# InterfacesB_CONNECTORS.net
KiCad netlist of a schematic drawn in Altium Designer
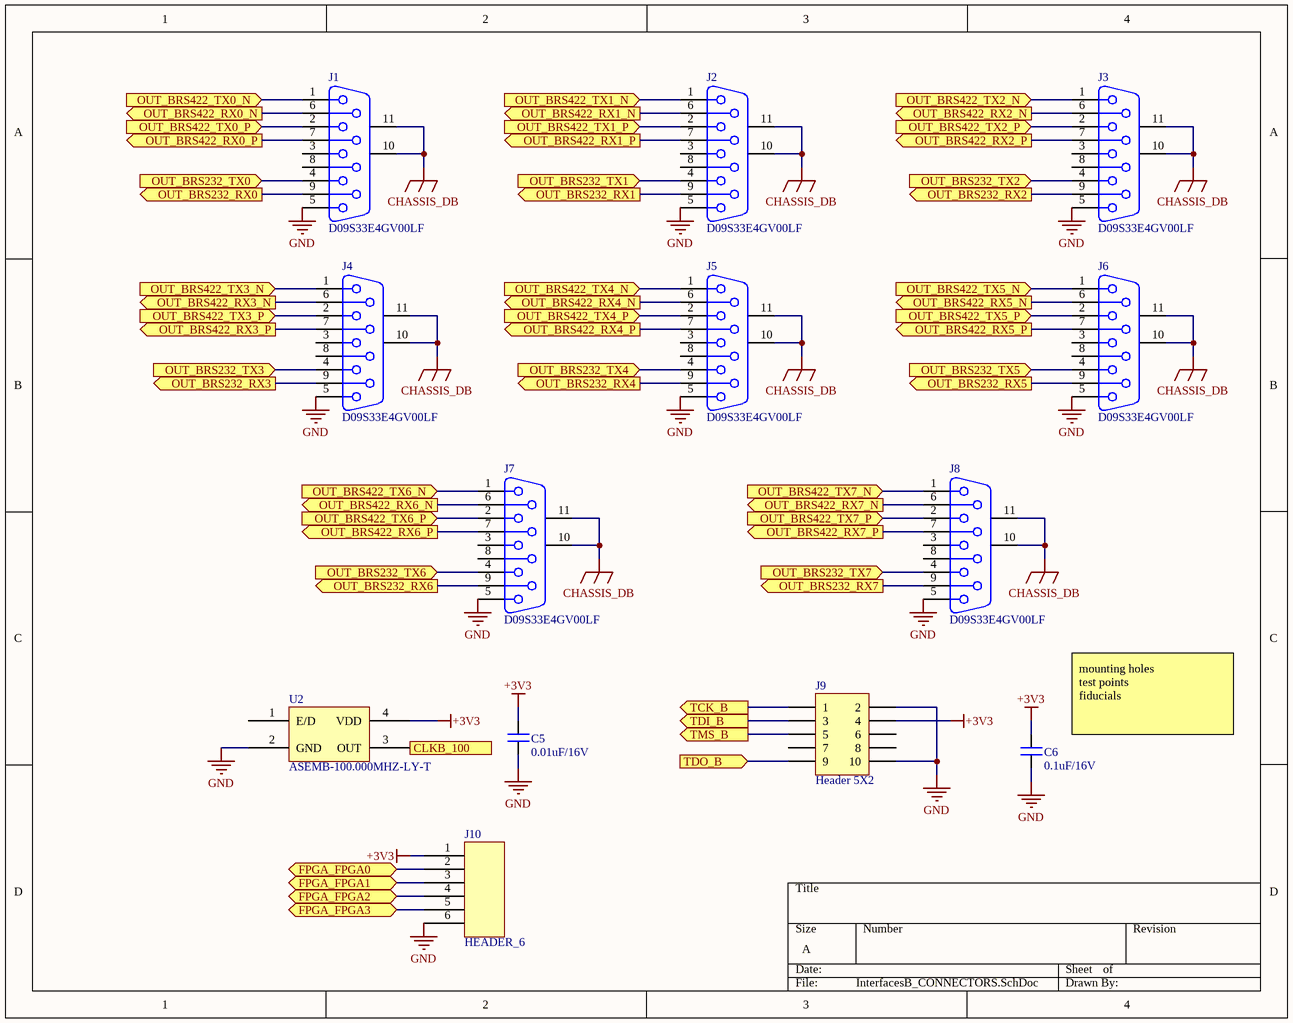
[diagram p0: InterfacesB_CONNECTORS.SchDoc]

(export (version "E")
  (design (tool "Eeschema 10.0.6"))
  (components
    (comp (ref "C5")
      (value "0.01uF/16V")
      (footprint "CAP_0805")
      (fields (field (name "Comment") "CAP_0805"))
      (libsource (lib "AdapterLib") (part "CAP_0805"))
    )
    (comp (ref "C6")
      (value "0.1uF/16V")
      (footprint "CAP_0805")
      (fields (field (name "Comment") "CAP_0805"))
      (libsource (lib "AdapterLib") (part "CAP_0805"))
    )
    (comp (ref "J1")
      (value "D09S33E4GV00LF")
      (footprint "D09S33E4GV00LF")
      (libsource (lib "AdapterLib") (part "D09S33E4GV00LF"))
    )
    (comp (ref "J2")
      (value "D09S33E4GV00LF")
      (footprint "D09S33E4GV00LF")
      (libsource (lib "AdapterLib") (part "D09S33E4GV00LF"))
    )
    (comp (ref "J3")
      (value "D09S33E4GV00LF")
      (footprint "D09S33E4GV00LF")
      (libsource (lib "AdapterLib") (part "D09S33E4GV00LF"))
    )
    (comp (ref "J4")
      (value "D09S33E4GV00LF")
      (footprint "D09S33E4GV00LF")
      (libsource (lib "AdapterLib") (part "D09S33E4GV00LF"))
    )
    (comp (ref "J5")
      (value "D09S33E4GV00LF")
      (footprint "D09S33E4GV00LF")
      (libsource (lib "AdapterLib") (part "D09S33E4GV00LF"))
    )
    (comp (ref "J6")
      (value "D09S33E4GV00LF")
      (footprint "D09S33E4GV00LF")
      (libsource (lib "AdapterLib") (part "D09S33E4GV00LF"))
    )
    (comp (ref "J7")
      (value "D09S33E4GV00LF")
      (footprint "D09S33E4GV00LF")
      (libsource (lib "AdapterLib") (part "D09S33E4GV00LF"))
    )
    (comp (ref "J8")
      (value "D09S33E4GV00LF")
      (footprint "D09S33E4GV00LF")
      (libsource (lib "AdapterLib") (part "D09S33E4GV00LF"))
    )
    (comp (ref "J9")
      (value "Header 5X2")
      (footprint "HEADER 5x2")
      (description "Header, 5-Pin, Dual row")
      (fields (field (name "PUBLISHER") "Altium Limited"))
      (libsource (lib "AdapterLib") (part "Header 5X2"))
    )
    (comp (ref "J10")
      (value "HEADER_6")
      (footprint "HEADER_6")
      (libsource (lib "AdapterLib") (part "HEADER_6"))
    )
    (comp (ref "U2")
      (value "ASEMB-100.000MHZ-LY-T")
      (footprint "ASEMB-100.000MHZ-LY-T")
      (libsource (lib "AdapterLib") (part "ASEMB-100.000MHZ-LY-T"))
    )
  )
  (nets
    (net (code "1") (name "+3V3") (class "Default")
      (node (ref "C5") (pin "2") (pinfunction "2_2") (pintype "passive"))
      (node (ref "C6") (pin "2") (pinfunction "2_2") (pintype "passive"))
      (node (ref "J10") (pin "1") (pintype "passive"))
      (node (ref "J9") (pin "4") (pinfunction "4_4") (pintype "passive"))
      (node (ref "U2") (pin "4") (pinfunction "VDD_4") (pintype "passive"))
    )
    (net (code "2") (name "/CLKB_100") (class "Default")
      (node (ref "U2") (pin "3") (pinfunction "OUT_3") (pintype "passive"))
    )
    (net (code "3") (name "/FPGA_FPGA0") (class "Default") (node (ref "J10") (pin "2") (pintype "passive")))
    (net (code "4") (name "/FPGA_FPGA1") (class "Default") (node (ref "J10") (pin "3") (pintype "passive")))
    (net (code "5") (name "/FPGA_FPGA2") (class "Default") (node (ref "J10") (pin "4") (pintype "passive")))
    (net (code "6") (name "/FPGA_FPGA3") (class "Default") (node (ref "J10") (pin "5") (pintype "passive")))
    (net (code "7") (name "/OUT_BRS232_RX0") (class "Default")
      (node (ref "J1") (pin "9") (pinfunction "9_9") (pintype "passive"))
    )
    (net (code "8") (name "/OUT_BRS232_RX1") (class "Default")
      (node (ref "J2") (pin "9") (pinfunction "9_9") (pintype "passive"))
    )
    (net (code "9") (name "/OUT_BRS232_RX2") (class "Default")
      (node (ref "J3") (pin "9") (pinfunction "9_9") (pintype "passive"))
    )
    (net (code "10") (name "/OUT_BRS232_RX3") (class "Default")
      (node (ref "J4") (pin "9") (pinfunction "9_9") (pintype "passive"))
    )
    (net (code "11") (name "/OUT_BRS232_RX4") (class "Default")
      (node (ref "J5") (pin "9") (pinfunction "9_9") (pintype "passive"))
    )
    (net (code "12") (name "/OUT_BRS232_RX5") (class "Default")
      (node (ref "J6") (pin "9") (pinfunction "9_9") (pintype "passive"))
    )
    (net (code "13") (name "/OUT_BRS232_RX6") (class "Default")
      (node (ref "J7") (pin "9") (pinfunction "9_9") (pintype "passive"))
    )
    (net (code "14") (name "/OUT_BRS232_RX7") (class "Default")
      (node (ref "J8") (pin "9") (pinfunction "9_9") (pintype "passive"))
    )
    (net (code "15") (name "/OUT_BRS232_TX0") (class "Default")
      (node (ref "J1") (pin "4") (pinfunction "4_4") (pintype "passive"))
    )
    (net (code "16") (name "/OUT_BRS232_TX1") (class "Default")
      (node (ref "J2") (pin "4") (pinfunction "4_4") (pintype "passive"))
    )
    (net (code "17") (name "/OUT_BRS232_TX2") (class "Default")
      (node (ref "J3") (pin "4") (pinfunction "4_4") (pintype "passive"))
    )
    (net (code "18") (name "/OUT_BRS232_TX3") (class "Default")
      (node (ref "J4") (pin "4") (pinfunction "4_4") (pintype "passive"))
    )
    (net (code "19") (name "/OUT_BRS232_TX4") (class "Default")
      (node (ref "J5") (pin "4") (pinfunction "4_4") (pintype "passive"))
    )
    (net (code "20") (name "/OUT_BRS232_TX5") (class "Default")
      (node (ref "J6") (pin "4") (pinfunction "4_4") (pintype "passive"))
    )
    (net (code "21") (name "/OUT_BRS232_TX6") (class "Default")
      (node (ref "J7") (pin "4") (pinfunction "4_4") (pintype "passive"))
    )
    (net (code "22") (name "/OUT_BRS232_TX7") (class "Default")
      (node (ref "J8") (pin "4") (pinfunction "4_4") (pintype "passive"))
    )
    (net (code "23") (name "/OUT_BRS422_RX0_N") (class "Default")
      (node (ref "J1") (pin "6") (pinfunction "6_6") (pintype "passive"))
    )
    (net (code "24") (name "/OUT_BRS422_RX0_P") (class "Default")
      (node (ref "J1") (pin "7") (pinfunction "7_7") (pintype "passive"))
    )
    (net (code "25") (name "/OUT_BRS422_RX1_N") (class "Default")
      (node (ref "J2") (pin "6") (pinfunction "6_6") (pintype "passive"))
    )
    (net (code "26") (name "/OUT_BRS422_RX1_P") (class "Default")
      (node (ref "J2") (pin "7") (pinfunction "7_7") (pintype "passive"))
    )
    (net (code "27") (name "/OUT_BRS422_RX2_N") (class "Default")
      (node (ref "J3") (pin "6") (pinfunction "6_6") (pintype "passive"))
    )
    (net (code "28") (name "/OUT_BRS422_RX2_P") (class "Default")
      (node (ref "J3") (pin "7") (pinfunction "7_7") (pintype "passive"))
    )
    (net (code "29") (name "/OUT_BRS422_RX3_N") (class "Default")
      (node (ref "J4") (pin "6") (pinfunction "6_6") (pintype "passive"))
    )
    (net (code "30") (name "/OUT_BRS422_RX3_P") (class "Default")
      (node (ref "J4") (pin "7") (pinfunction "7_7") (pintype "passive"))
    )
    (net (code "31") (name "/OUT_BRS422_RX4_N") (class "Default")
      (node (ref "J5") (pin "6") (pinfunction "6_6") (pintype "passive"))
    )
    (net (code "32") (name "/OUT_BRS422_RX4_P") (class "Default")
      (node (ref "J5") (pin "7") (pinfunction "7_7") (pintype "passive"))
    )
    (net (code "33") (name "/OUT_BRS422_RX5_N") (class "Default")
      (node (ref "J6") (pin "6") (pinfunction "6_6") (pintype "passive"))
    )
    (net (code "34") (name "/OUT_BRS422_RX5_P") (class "Default")
      (node (ref "J6") (pin "7") (pinfunction "7_7") (pintype "passive"))
    )
    (net (code "35") (name "/OUT_BRS422_RX6_N") (class "Default")
      (node (ref "J7") (pin "6") (pinfunction "6_6") (pintype "passive"))
    )
    (net (code "36") (name "/OUT_BRS422_RX6_P") (class "Default")
      (node (ref "J7") (pin "7") (pinfunction "7_7") (pintype "passive"))
    )
    (net (code "37") (name "/OUT_BRS422_RX7_N") (class "Default")
      (node (ref "J8") (pin "6") (pinfunction "6_6") (pintype "passive"))
    )
    (net (code "38") (name "/OUT_BRS422_RX7_P") (class "Default")
      (node (ref "J8") (pin "7") (pinfunction "7_7") (pintype "passive"))
    )
    (net (code "39") (name "/OUT_BRS422_TX0_N") (class "Default")
      (node (ref "J1") (pin "1") (pinfunction "1_1") (pintype "passive"))
    )
    (net (code "40") (name "/OUT_BRS422_TX0_P") (class "Default")
      (node (ref "J1") (pin "2") (pinfunction "2_2") (pintype "passive"))
    )
    (net (code "41") (name "/OUT_BRS422_TX1_N") (class "Default")
      (node (ref "J2") (pin "1") (pinfunction "1_1") (pintype "passive"))
    )
    (net (code "42") (name "/OUT_BRS422_TX1_P") (class "Default")
      (node (ref "J2") (pin "2") (pinfunction "2_2") (pintype "passive"))
    )
    (net (code "43") (name "/OUT_BRS422_TX2_N") (class "Default")
      (node (ref "J3") (pin "1") (pinfunction "1_1") (pintype "passive"))
    )
    (net (code "44") (name "/OUT_BRS422_TX2_P") (class "Default")
      (node (ref "J3") (pin "2") (pinfunction "2_2") (pintype "passive"))
    )
    (net (code "45") (name "/OUT_BRS422_TX3_N") (class "Default")
      (node (ref "J4") (pin "1") (pinfunction "1_1") (pintype "passive"))
    )
    (net (code "46") (name "/OUT_BRS422_TX3_P") (class "Default")
      (node (ref "J4") (pin "2") (pinfunction "2_2") (pintype "passive"))
    )
    (net (code "47") (name "/OUT_BRS422_TX4_N") (class "Default")
      (node (ref "J5") (pin "1") (pinfunction "1_1") (pintype "passive"))
    )
    (net (code "48") (name "/OUT_BRS422_TX4_P") (class "Default")
      (node (ref "J5") (pin "2") (pinfunction "2_2") (pintype "passive"))
    )
    (net (code "49") (name "/OUT_BRS422_TX5_N") (class "Default")
      (node (ref "J6") (pin "1") (pinfunction "1_1") (pintype "passive"))
    )
    (net (code "50") (name "/OUT_BRS422_TX5_P") (class "Default")
      (node (ref "J6") (pin "2") (pinfunction "2_2") (pintype "passive"))
    )
    (net (code "51") (name "/OUT_BRS422_TX6_N") (class "Default")
      (node (ref "J7") (pin "1") (pinfunction "1_1") (pintype "passive"))
    )
    (net (code "52") (name "/OUT_BRS422_TX6_P") (class "Default")
      (node (ref "J7") (pin "2") (pinfunction "2_2") (pintype "passive"))
    )
    (net (code "53") (name "/OUT_BRS422_TX7_N") (class "Default")
      (node (ref "J8") (pin "1") (pinfunction "1_1") (pintype "passive"))
    )
    (net (code "54") (name "/OUT_BRS422_TX7_P") (class "Default")
      (node (ref "J8") (pin "2") (pinfunction "2_2") (pintype "passive"))
    )
    (net (code "55") (name "/TCK_B") (class "Default")
      (node (ref "J9") (pin "1") (pinfunction "1_1") (pintype "passive"))
    )
    (net (code "56") (name "/TDI_B") (class "Default")
      (node (ref "J9") (pin "3") (pinfunction "3_3") (pintype "passive"))
    )
    (net (code "57") (name "/TDO_B") (class "Default")
      (node (ref "J9") (pin "9") (pinfunction "9_9") (pintype "passive"))
    )
    (net (code "58") (name "/TMS_B") (class "Default")
      (node (ref "J9") (pin "5") (pinfunction "5_5") (pintype "passive"))
    )
    (net (code "59") (name "CHASSIS_DB") (class "Default")
      (node (ref "J1") (pin "10") (pinfunction "MH1_10") (pintype "passive"))
      (node (ref "J1") (pin "11") (pinfunction "MH2_11") (pintype "passive"))
      (node (ref "J2") (pin "10") (pinfunction "MH1_10") (pintype "passive"))
      (node (ref "J2") (pin "11") (pinfunction "MH2_11") (pintype "passive"))
      (node (ref "J3") (pin "10") (pinfunction "MH1_10") (pintype "passive"))
      (node (ref "J3") (pin "11") (pinfunction "MH2_11") (pintype "passive"))
      (node (ref "J4") (pin "10") (pinfunction "MH1_10") (pintype "passive"))
      (node (ref "J4") (pin "11") (pinfunction "MH2_11") (pintype "passive"))
      (node (ref "J5") (pin "10") (pinfunction "MH1_10") (pintype "passive"))
      (node (ref "J5") (pin "11") (pinfunction "MH2_11") (pintype "passive"))
      (node (ref "J6") (pin "10") (pinfunction "MH1_10") (pintype "passive"))
      (node (ref "J6") (pin "11") (pinfunction "MH2_11") (pintype "passive"))
      (node (ref "J7") (pin "10") (pinfunction "MH1_10") (pintype "passive"))
      (node (ref "J7") (pin "11") (pinfunction "MH2_11") (pintype "passive"))
      (node (ref "J8") (pin "10") (pinfunction "MH1_10") (pintype "passive"))
      (node (ref "J8") (pin "11") (pinfunction "MH2_11") (pintype "passive"))
    )
    (net (code "60") (name "GND") (class "Default")
      (node (ref "C5") (pin "1") (pinfunction "1_1") (pintype "passive"))
      (node (ref "C6") (pin "1") (pinfunction "1_1") (pintype "passive"))
      (node (ref "J1") (pin "5") (pinfunction "5_5") (pintype "passive"))
      (node (ref "J10") (pin "6") (pintype "passive"))
      (node (ref "J2") (pin "5") (pinfunction "5_5") (pintype "passive"))
      (node (ref "J3") (pin "5") (pinfunction "5_5") (pintype "passive"))
      (node (ref "J4") (pin "5") (pinfunction "5_5") (pintype "passive"))
      (node (ref "J5") (pin "5") (pinfunction "5_5") (pintype "passive"))
      (node (ref "J6") (pin "5") (pinfunction "5_5") (pintype "passive"))
      (node (ref "J7") (pin "5") (pinfunction "5_5") (pintype "passive"))
      (node (ref "J8") (pin "5") (pinfunction "5_5") (pintype "passive"))
      (node (ref "J9") (pin "10") (pinfunction "10_10") (pintype "passive"))
      (node (ref "J9") (pin "2") (pinfunction "2_2") (pintype "passive"))
      (node (ref "U2") (pin "2") (pinfunction "GND_2") (pintype "passive"))
    )
    (net (code "61") (name "unconnected-(J1-Pad3)") (class "Default")
      (node (ref "J1") (pin "3") (pinfunction "3_3") (pintype "passive"))
    )
    (net (code "62") (name "unconnected-(J1-Pad8)") (class "Default")
      (node (ref "J1") (pin "8") (pinfunction "8_8") (pintype "passive"))
    )
    (net (code "63") (name "unconnected-(J2-Pad3)") (class "Default")
      (node (ref "J2") (pin "3") (pinfunction "3_3") (pintype "passive"))
    )
    (net (code "64") (name "unconnected-(J2-Pad8)") (class "Default")
      (node (ref "J2") (pin "8") (pinfunction "8_8") (pintype "passive"))
    )
    (net (code "65") (name "unconnected-(J3-Pad3)") (class "Default")
      (node (ref "J3") (pin "3") (pinfunction "3_3") (pintype "passive"))
    )
    (net (code "66") (name "unconnected-(J3-Pad8)") (class "Default")
      (node (ref "J3") (pin "8") (pinfunction "8_8") (pintype "passive"))
    )
    (net (code "67") (name "unconnected-(J4-Pad3)") (class "Default")
      (node (ref "J4") (pin "3") (pinfunction "3_3") (pintype "passive"))
    )
    (net (code "68") (name "unconnected-(J4-Pad8)") (class "Default")
      (node (ref "J4") (pin "8") (pinfunction "8_8") (pintype "passive"))
    )
    (net (code "69") (name "unconnected-(J5-Pad3)") (class "Default")
      (node (ref "J5") (pin "3") (pinfunction "3_3") (pintype "passive"))
    )
    (net (code "70") (name "unconnected-(J5-Pad8)") (class "Default")
      (node (ref "J5") (pin "8") (pinfunction "8_8") (pintype "passive"))
    )
    (net (code "71") (name "unconnected-(J6-Pad3)") (class "Default")
      (node (ref "J6") (pin "3") (pinfunction "3_3") (pintype "passive"))
    )
    (net (code "72") (name "unconnected-(J6-Pad8)") (class "Default")
      (node (ref "J6") (pin "8") (pinfunction "8_8") (pintype "passive"))
    )
    (net (code "73") (name "unconnected-(J7-Pad3)") (class "Default")
      (node (ref "J7") (pin "3") (pinfunction "3_3") (pintype "passive"))
    )
    (net (code "74") (name "unconnected-(J7-Pad8)") (class "Default")
      (node (ref "J7") (pin "8") (pinfunction "8_8") (pintype "passive"))
    )
    (net (code "75") (name "unconnected-(J8-Pad3)") (class "Default")
      (node (ref "J8") (pin "3") (pinfunction "3_3") (pintype "passive"))
    )
    (net (code "76") (name "unconnected-(J8-Pad8)") (class "Default")
      (node (ref "J8") (pin "8") (pinfunction "8_8") (pintype "passive"))
    )
    (net (code "77") (name "unconnected-(J9-Pad6)") (class "Default")
      (node (ref "J9") (pin "6") (pinfunction "6_6") (pintype "passive"))
    )
    (net (code "78") (name "unconnected-(J9-Pad7)") (class "Default")
      (node (ref "J9") (pin "7") (pinfunction "7_7") (pintype "passive"))
    )
    (net (code "79") (name "unconnected-(J9-Pad8)") (class "Default")
      (node (ref "J9") (pin "8") (pinfunction "8_8") (pintype "passive"))
    )
    (net (code "80") (name "unconnected-(U2-E{slash}D-Pad1)") (class "Default")
      (node (ref "U2") (pin "1") (pinfunction "E/D_1") (pintype "passive"))
    )
  )
)
